# Copy_of_SX1276_e266v02a.net
KiCad netlist of a schematic drawn in Altium Designer
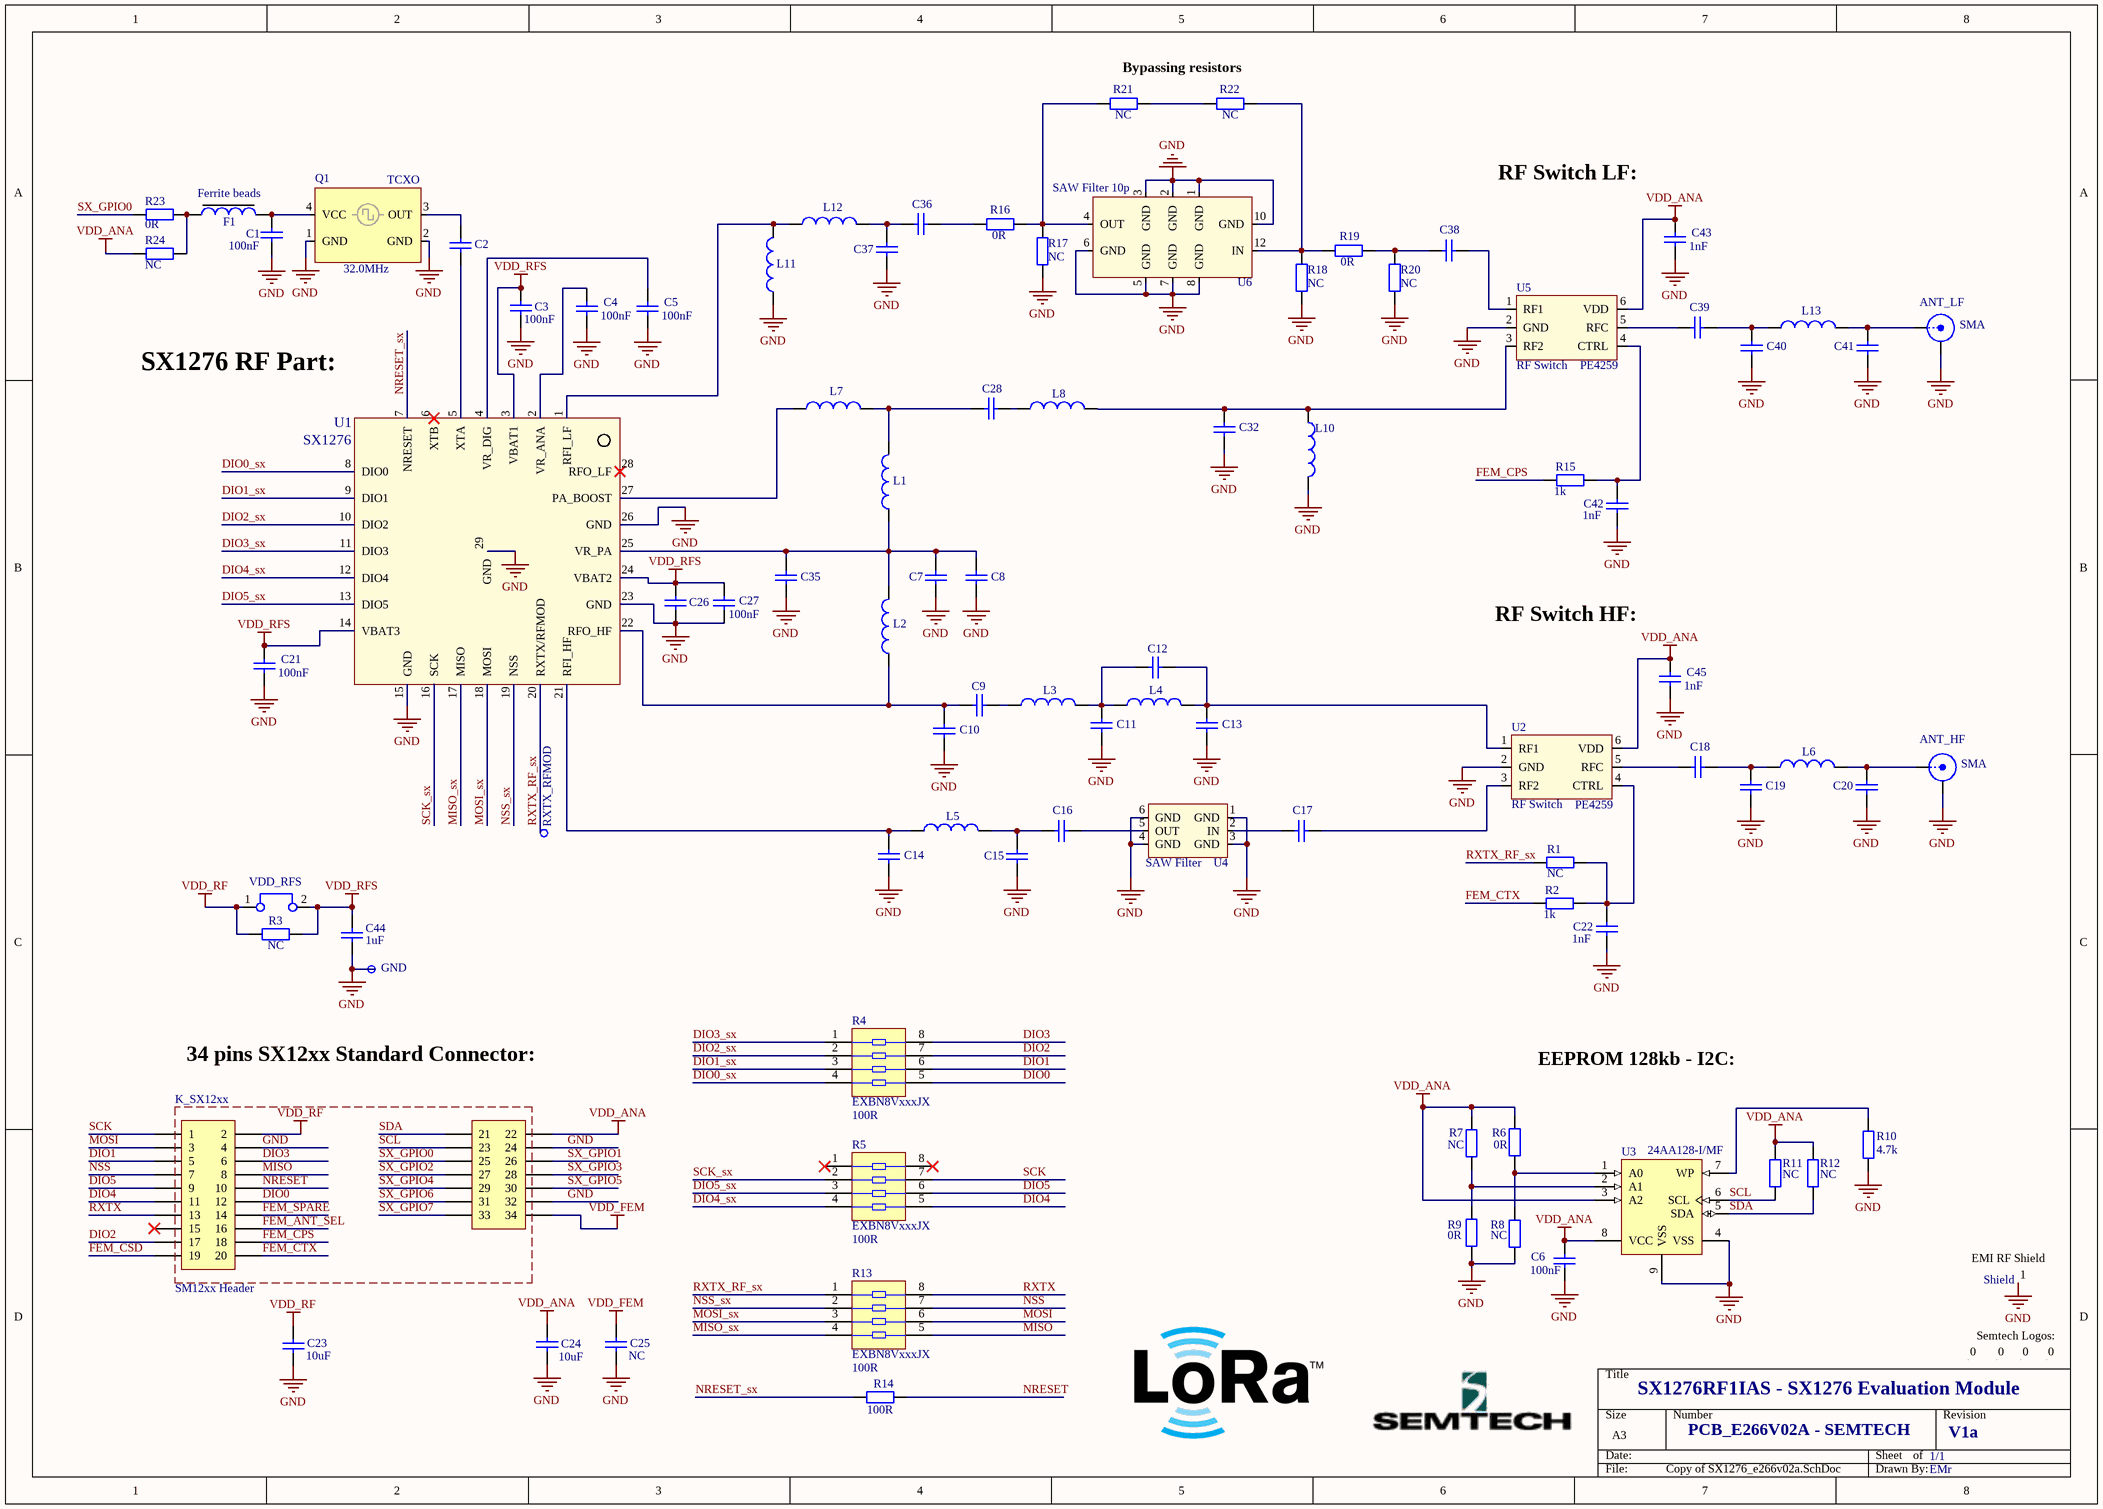
[diagram p0: Copy of SX1276_e266v02a.SchDoc]

(export (version "E")
  (design (tool "Eeschema 10.0.6"))
  (components
    (comp (ref "ANT_HF")
      (value "SMA")
      (footprint "SMA END LAUNCH JACK RECEPTACLE SHORT")
      (description "SMA Straight Connector")
      (fields (field (name "PUBLISHER") "Altium Limited"))
      (libsource (lib "SX1276_e266v02a") (part "SMA"))
    )
    (comp (ref "ANT_LF")
      (value "SMA")
      (footprint "SMA END LAUNCH JACK RECEPTACLE SHORT")
      (description "SMA Straight Connector")
      (fields (field (name "PUBLISHER") "Altium Limited"))
      (libsource (lib "SX1276_e266v02a") (part "SMA"))
    )
    (comp (ref "C1")
      (value "100nF")
      (footprint "rlc_402_smd")
      (description "Capacitor SMD")
      (fields (field (name "Comment") "Cap") (field (name "PUBLISHER") "Altium Limited"))
      (libsource (lib "SX1276_e266v02a") (part "Cap"))
    )
    (comp (ref "C2")
      (value "Cap")
      (footprint "rlc_402_smd")
      (description "Capacitor SMD")
      (fields (field (name "PUBLISHER") "Altium Limited"))
      (libsource (lib "SX1276_e266v02a") (part "Cap"))
    )
    (comp (ref "C3")
      (value "100nF")
      (footprint "rlc_402_smd")
      (description "Capacitor SMD")
      (fields (field (name "Comment") "Cap") (field (name "PUBLISHER") "Altium Limited"))
      (libsource (lib "SX1276_e266v02a") (part "Cap"))
    )
    (comp (ref "C4")
      (value "100nF")
      (footprint "rlc_402_smd")
      (description "Capacitor SMD")
      (fields (field (name "Comment") "Cap") (field (name "PUBLISHER") "Altium Limited"))
      (libsource (lib "SX1276_e266v02a") (part "Cap"))
    )
    (comp (ref "C5")
      (value "100nF")
      (footprint "rlc_402_smd")
      (description "Capacitor SMD")
      (fields (field (name "Comment") "Cap") (field (name "PUBLISHER") "Altium Limited"))
      (libsource (lib "SX1276_e266v02a") (part "Cap"))
    )
    (comp (ref "C6")
      (value "100nF")
      (footprint "rlc_402_smd")
      (description "Capacitor SMD")
      (fields (field (name "Comment") "Cap") (field (name "PUBLISHER") "Altium Limited"))
      (libsource (lib "SX1276_e266v02a") (part "Cap"))
    )
    (comp (ref "C7")
      (value "Cap")
      (footprint "rlc_402_smd")
      (description "Capacitor SMD")
      (fields (field (name "PUBLISHER") "Altium Limited"))
      (libsource (lib "SX1276_e266v02a") (part "Cap"))
    )
    (comp (ref "C8")
      (value "Cap")
      (footprint "rlc_402_smd")
      (description "Capacitor SMD")
      (fields (field (name "PUBLISHER") "Altium Limited"))
      (libsource (lib "SX1276_e266v02a") (part "Cap"))
    )
    (comp (ref "C9")
      (value "Cap")
      (footprint "rlc_402_smd")
      (description "Capacitor SMD")
      (fields (field (name "PUBLISHER") "Altium Limited"))
      (libsource (lib "SX1276_e266v02a") (part "Cap"))
    )
    (comp (ref "C10")
      (value "Cap")
      (footprint "rlc_402_smd")
      (description "Capacitor SMD")
      (fields (field (name "PUBLISHER") "Altium Limited"))
      (libsource (lib "SX1276_e266v02a") (part "Cap"))
    )
    (comp (ref "C11")
      (value "Cap")
      (footprint "rlc_402_smd")
      (description "Capacitor SMD")
      (fields (field (name "PUBLISHER") "Altium Limited"))
      (libsource (lib "SX1276_e266v02a") (part "Cap"))
    )
    (comp (ref "C12")
      (value "Cap")
      (footprint "rlc_402_smd")
      (description "Capacitor SMD")
      (fields (field (name "PUBLISHER") "Altium Limited"))
      (libsource (lib "SX1276_e266v02a") (part "Cap"))
    )
    (comp (ref "C13")
      (value "Cap")
      (footprint "rlc_402_smd")
      (description "Capacitor SMD")
      (fields (field (name "PUBLISHER") "Altium Limited"))
      (libsource (lib "SX1276_e266v02a") (part "Cap"))
    )
    (comp (ref "C14")
      (value "Cap")
      (footprint "rlc_402_smd")
      (description "Capacitor SMD")
      (fields (field (name "PUBLISHER") "Altium Limited"))
      (libsource (lib "SX1276_e266v02a") (part "Cap"))
    )
    (comp (ref "C15")
      (value "Cap")
      (footprint "rlc_402_smd")
      (description "Capacitor SMD")
      (fields (field (name "PUBLISHER") "Altium Limited"))
      (libsource (lib "SX1276_e266v02a") (part "Cap"))
    )
    (comp (ref "C16")
      (value "Cap")
      (footprint "rlc_402_smd")
      (description "Capacitor SMD")
      (fields (field (name "PUBLISHER") "Altium Limited"))
      (libsource (lib "SX1276_e266v02a") (part "Cap"))
    )
    (comp (ref "C17")
      (value "Cap")
      (footprint "rlc_402_smd")
      (description "Capacitor SMD")
      (fields (field (name "PUBLISHER") "Altium Limited"))
      (libsource (lib "SX1276_e266v02a") (part "Cap"))
    )
    (comp (ref "C18")
      (value "Cap")
      (footprint "rlc_402_smd")
      (description "Capacitor SMD")
      (fields (field (name "PUBLISHER") "Altium Limited"))
      (libsource (lib "SX1276_e266v02a") (part "Cap"))
    )
    (comp (ref "C19")
      (value "Cap")
      (footprint "rlc_402_smd")
      (description "Capacitor SMD")
      (fields (field (name "PUBLISHER") "Altium Limited"))
      (libsource (lib "SX1276_e266v02a") (part "Cap"))
    )
    (comp (ref "C20")
      (value "Cap")
      (footprint "rlc_402_smd")
      (description "Capacitor SMD")
      (fields (field (name "PUBLISHER") "Altium Limited"))
      (libsource (lib "SX1276_e266v02a") (part "Cap"))
    )
    (comp (ref "C21")
      (value "100nF")
      (footprint "rlc_402_smd")
      (description "Capacitor SMD")
      (fields (field (name "Comment") "Cap") (field (name "PUBLISHER") "Altium Limited"))
      (libsource (lib "SX1276_e266v02a") (part "Cap"))
    )
    (comp (ref "C22")
      (value "1nF")
      (footprint "rlc_402_smd")
      (description "Capacitor SMD")
      (fields (field (name "Comment") "Cap") (field (name "PUBLISHER") "Altium Limited"))
      (libsource (lib "SX1276_e266v02a") (part "Cap"))
    )
    (comp (ref "C23")
      (value "10uF")
      (footprint "rlc_805_smd")
      (description "Capacitor SMD")
      (fields (field (name "Comment") "Cap") (field (name "PUBLISHER") "Altium Limited"))
      (libsource (lib "SX1276_e266v02a") (part "Cap"))
    )
    (comp (ref "C24")
      (value "10uF")
      (footprint "rlc_805_smd")
      (description "Capacitor SMD")
      (fields (field (name "Comment") "Cap") (field (name "PUBLISHER") "Altium Limited"))
      (libsource (lib "SX1276_e266v02a") (part "Cap"))
    )
    (comp (ref "C25")
      (value "NC")
      (footprint "rlc_805_smd")
      (description "Capacitor SMD")
      (fields (field (name "Comment") "Cap") (field (name "PUBLISHER") "Altium Limited"))
      (libsource (lib "SX1276_e266v02a") (part "Cap"))
    )
    (comp (ref "C26")
      (value "Cap")
      (footprint "rlc_402_smd")
      (description "Capacitor SMD")
      (fields (field (name "PUBLISHER") "Altium Limited"))
      (libsource (lib "SX1276_e266v02a") (part "Cap"))
    )
    (comp (ref "C27")
      (value "100nF")
      (footprint "rlc_402_smd")
      (description "Capacitor SMD")
      (fields (field (name "Comment") "Cap") (field (name "PUBLISHER") "Altium Limited"))
      (libsource (lib "SX1276_e266v02a") (part "Cap"))
    )
    (comp (ref "C28")
      (value "Cap")
      (footprint "rlc_402_smd")
      (description "Capacitor SMD")
      (fields (field (name "PUBLISHER") "Altium Limited"))
      (libsource (lib "SX1276_e266v02a") (part "Cap"))
    )
    (comp (ref "C32")
      (value "Cap")
      (footprint "rlc_402_smd")
      (description "Capacitor SMD")
      (fields (field (name "PUBLISHER") "Altium Limited"))
      (libsource (lib "SX1276_e266v02a") (part "Cap"))
    )
    (comp (ref "C35")
      (value "Cap")
      (footprint "rlc_402_smd")
      (description "Capacitor SMD")
      (fields (field (name "PUBLISHER") "Altium Limited"))
      (libsource (lib "SX1276_e266v02a") (part "Cap"))
    )
    (comp (ref "C36")
      (value "Cap")
      (footprint "rlc_402_smd")
      (description "Capacitor SMD")
      (fields (field (name "PUBLISHER") "Altium Limited"))
      (libsource (lib "SX1276_e266v02a") (part "Cap"))
    )
    (comp (ref "C37")
      (value "Cap")
      (footprint "rlc_402_smd")
      (description "Capacitor SMD")
      (fields (field (name "PUBLISHER") "Altium Limited"))
      (libsource (lib "SX1276_e266v02a") (part "Cap"))
    )
    (comp (ref "C38")
      (value "Cap")
      (footprint "rlc_402_smd")
      (description "Capacitor SMD")
      (fields (field (name "PUBLISHER") "Altium Limited"))
      (libsource (lib "SX1276_e266v02a") (part "Cap"))
    )
    (comp (ref "C39")
      (value "Cap")
      (footprint "rlc_402_smd")
      (description "Capacitor SMD")
      (fields (field (name "PUBLISHER") "Altium Limited"))
      (libsource (lib "SX1276_e266v02a") (part "Cap"))
    )
    (comp (ref "C40")
      (value "Cap")
      (footprint "rlc_402_smd")
      (description "Capacitor SMD")
      (fields (field (name "PUBLISHER") "Altium Limited"))
      (libsource (lib "SX1276_e266v02a") (part "Cap"))
    )
    (comp (ref "C41")
      (value "Cap")
      (footprint "rlc_402_smd")
      (description "Capacitor SMD")
      (fields (field (name "PUBLISHER") "Altium Limited"))
      (libsource (lib "SX1276_e266v02a") (part "Cap"))
    )
    (comp (ref "C42")
      (value "1nF")
      (footprint "rlc_402_smd")
      (description "Capacitor SMD")
      (fields (field (name "Comment") "Cap") (field (name "PUBLISHER") "Altium Limited"))
      (libsource (lib "SX1276_e266v02a") (part "Cap"))
    )
    (comp (ref "C43")
      (value "1nF")
      (footprint "rlc_402_smd")
      (description "Capacitor SMD")
      (fields (field (name "Comment") "Cap") (field (name "PUBLISHER") "Altium Limited"))
      (libsource (lib "SX1276_e266v02a") (part "Cap"))
    )
    (comp (ref "C44")
      (value "1uF")
      (footprint "rlc_603_smd")
      (description "Capacitor (Semiconductor SIM Model)")
      (fields (field (name "Comment") "Cap Semi") (field (name "PUBLISHER") "Altium Limited"))
      (libsource (lib "SX1276_e266v02a") (part "Cap Semi"))
    )
    (comp (ref "C45")
      (value "1nF")
      (footprint "rlc_402_smd")
      (description "Capacitor SMD")
      (fields (field (name "Comment") "Cap") (field (name "PUBLISHER") "Altium Limited"))
      (libsource (lib "SX1276_e266v02a") (part "Cap"))
    )
    (comp (ref "F1")
      (value "Ferrite beads")
      (footprint "rlc_402_smd")
      (libsource (lib "SX1276_e266v02a") (part "Ferrite beads"))
    )
    (comp (ref "GND")
      (value "Test Pin")
      (footprint "pin_1mm")
      (libsource (lib "SX1276_e266v02a") (part "test_pin"))
    )
    (comp (ref "K_SX12xx")
      (value "SM12xx Header")
      (footprint "HDR34 Header")
      (description "SM12xx Header; 34pins: 2x10pins + 2x7pins")
      (fields (field (name "PUBLISHER") "Altium Limited"))
      (libsource (lib "SX1276_e266v02a") (part "SM12xx Header"))
    )
    (comp (ref "L1")
      (value "Inductor")
      (footprint "rlc_402_smd")
      (description "Inductor SMD")
      (fields (field (name "PUBLISHER") "Altium Limited"))
      (libsource (lib "SX1276_e266v02a") (part "Inductor"))
    )
    (comp (ref "L2")
      (value "Inductor")
      (footprint "rlc_402_smd")
      (description "Inductor SMD")
      (fields (field (name "PUBLISHER") "Altium Limited"))
      (libsource (lib "SX1276_e266v02a") (part "Inductor"))
    )
    (comp (ref "L3")
      (value "Inductor")
      (footprint "rlc_402_smd")
      (description "Inductor SMD")
      (fields (field (name "PUBLISHER") "Altium Limited"))
      (libsource (lib "SX1276_e266v02a") (part "Inductor"))
    )
    (comp (ref "L4")
      (value "Inductor")
      (footprint "rlc_402_smd")
      (description "Inductor SMD")
      (fields (field (name "PUBLISHER") "Altium Limited"))
      (libsource (lib "SX1276_e266v02a") (part "Inductor"))
    )
    (comp (ref "L5")
      (value "Inductor")
      (footprint "rlc_402_smd")
      (description "Inductor SMD")
      (fields (field (name "PUBLISHER") "Altium Limited"))
      (libsource (lib "SX1276_e266v02a") (part "Inductor"))
    )
    (comp (ref "L6")
      (value "Inductor")
      (footprint "rlc_402_smd")
      (description "Inductor SMD")
      (fields (field (name "PUBLISHER") "Altium Limited"))
      (libsource (lib "SX1276_e266v02a") (part "Inductor"))
    )
    (comp (ref "L7")
      (value "Inductor")
      (footprint "rlc_402_smd")
      (description "Inductor SMD")
      (fields (field (name "PUBLISHER") "Altium Limited"))
      (libsource (lib "SX1276_e266v02a") (part "Inductor"))
    )
    (comp (ref "L8")
      (value "Inductor")
      (footprint "rlc_402_smd")
      (description "Inductor SMD")
      (fields (field (name "PUBLISHER") "Altium Limited"))
      (libsource (lib "SX1276_e266v02a") (part "Inductor"))
    )
    (comp (ref "L10")
      (value "Inductor")
      (footprint "rlc_402_smd")
      (description "Inductor SMD")
      (fields (field (name "PUBLISHER") "Altium Limited"))
      (libsource (lib "SX1276_e266v02a") (part "Inductor"))
    )
    (comp (ref "L11")
      (value "Inductor")
      (footprint "rlc_402_smd")
      (description "Inductor SMD")
      (fields (field (name "PUBLISHER") "Altium Limited"))
      (libsource (lib "SX1276_e266v02a") (part "Inductor"))
    )
    (comp (ref "L12")
      (value "Inductor")
      (footprint "rlc_402_smd")
      (description "Inductor SMD")
      (fields (field (name "PUBLISHER") "Altium Limited"))
      (libsource (lib "SX1276_e266v02a") (part "Inductor"))
    )
    (comp (ref "L13")
      (value "Inductor")
      (footprint "rlc_402_smd")
      (description "Inductor SMD")
      (fields (field (name "PUBLISHER") "Altium Limited"))
      (libsource (lib "SX1276_e266v02a") (part "Inductor"))
    )
    (comp (ref "Logo Bot")
      (value "Logo symbol")
      (footprint "logo_semtech_horiz_size3")
      (description "Schematic symbol for Logo")
      (libsource (lib "SX1276_e266v02a") (part "Logo"))
    )
    (comp (ref "Logo Lora Bot")
      (value "Logo symbol")
      (footprint "Logo LoRa Size4")
      (description "Schematic symbol for Logo")
      (libsource (lib "SX1276_e266v02a") (part "Logo"))
    )
    (comp (ref "Logo Lora Top")
      (value "Logo symbol")
      (footprint "Logo LoRa Size3")
      (description "Schematic symbol for Logo")
      (libsource (lib "SX1276_e266v02a") (part "Logo"))
    )
    (comp (ref "Logo Top")
      (value "Logo symbol")
      (footprint "logo_semtech_horiz_size2")
      (description "Schematic symbol for Logo")
      (libsource (lib "SX1276_e266v02a") (part "Logo"))
    )
    (comp (ref "Q1")
      (value "TCXO")
      (footprint "IT3200C TCXO")
      (fields (field (name "ALTIUM_VALUE") "32.0MHz"))
      (libsource (lib "SX1276_e266v02a") (part "TCXO"))
    )
    (comp (ref "R1")
      (value "NC")
      (footprint "rlc_402_smd")
      (description "Resistor SMD - IEC symbol version")
      (fields (field (name "Comment") "Resistor"))
      (libsource (lib "") (part "Resistor_3"))
    )
    (comp (ref "R2")
      (value "1k")
      (footprint "rlc_402_smd")
      (description "Resistor SMD - IEC symbol version")
      (fields (field (name "Comment") "Resistor"))
      (libsource (lib "") (part "Resistor_2"))
    )
    (comp (ref "R3")
      (value "NC")
      (footprint "rlc_805_smd")
      (description "Resistor SMD - IEC symbol version")
      (fields (field (name "Comment") "Resistor"))
      (libsource (lib "") (part "Resistor_2"))
    )
    (comp (ref "R4")
      (value "EXBN8VxxxJX")
      (footprint "EXB28V")
      (description "Mini-Flat Package, Isolated Resistor Network, 0.031 W/resistor")
      (fields (field (name "ALTIUM_VALUE") "100R"))
      (libsource (lib "SX1276_e266v02a") (part "EXBN8VxxxJX"))
    )
    (comp (ref "R5")
      (value "EXBN8VxxxJX")
      (footprint "EXB28V")
      (description "Mini-Flat Package, Isolated Resistor Network, 0.031 W/resistor")
      (fields (field (name "ALTIUM_VALUE") "100R"))
      (libsource (lib "SX1276_e266v02a") (part "EXBN8VxxxJX"))
    )
    (comp (ref "R6")
      (value "0R")
      (footprint "rlc_402_smd")
      (description "Resistor SMD - IEC symbol version")
      (fields (field (name "Comment") "Resistor"))
      (libsource (lib "") (part "Resistor_3"))
    )
    (comp (ref "R7")
      (value "NC")
      (footprint "rlc_402_smd")
      (description "Resistor SMD - IEC symbol version")
      (fields (field (name "Comment") "Resistor"))
      (libsource (lib "") (part "Resistor_3"))
    )
    (comp (ref "R8")
      (value "NC")
      (footprint "rlc_402_smd")
      (description "Resistor SMD - IEC symbol version")
      (fields (field (name "Comment") "Resistor"))
      (libsource (lib "") (part "Resistor_3"))
    )
    (comp (ref "R9")
      (value "0R")
      (footprint "rlc_402_smd")
      (description "Resistor SMD - IEC symbol version")
      (fields (field (name "Comment") "Resistor"))
      (libsource (lib "") (part "Resistor_3"))
    )
    (comp (ref "R10")
      (value "4.7k")
      (footprint "rlc_402_smd")
      (description "Resistor SMD - IEC symbol version")
      (fields (field (name "Comment") "Resistor"))
      (libsource (lib "") (part "Resistor_3"))
    )
    (comp (ref "R11")
      (value "NC")
      (footprint "rlc_402_smd")
      (description "Resistor SMD - IEC symbol version")
      (fields (field (name "Comment") "Resistor"))
      (libsource (lib "") (part "Resistor_3"))
    )
    (comp (ref "R12")
      (value "NC")
      (footprint "rlc_402_smd")
      (description "Resistor SMD - IEC symbol version")
      (fields (field (name "Comment") "Resistor"))
      (libsource (lib "") (part "Resistor_3"))
    )
    (comp (ref "R13")
      (value "EXBN8VxxxJX")
      (footprint "EXB28V")
      (description "Mini-Flat Package, Isolated Resistor Network, 0.031 W/resistor")
      (fields (field (name "ALTIUM_VALUE") "100R"))
      (libsource (lib "SX1276_e266v02a") (part "EXBN8VxxxJX"))
    )
    (comp (ref "R14")
      (value "100R")
      (footprint "rlc_402_smd")
      (description "Resistor SMD - IEC symbol version")
      (fields (field (name "Comment") "Resistor"))
      (libsource (lib "") (part "Resistor_1"))
    )
    (comp (ref "R15")
      (value "1k")
      (footprint "rlc_402_smd")
      (description "Resistor SMD - IEC symbol version")
      (fields (field (name "Comment") "Resistor"))
      (libsource (lib "") (part "Resistor_2"))
    )
    (comp (ref "R16")
      (value "0R")
      (footprint "rlc_402_smd")
      (description "Resistor SMD - IEC symbol version")
      (fields (field (name "Comment") "Resistor"))
      (libsource (lib "") (part "Resistor_2"))
    )
    (comp (ref "R17")
      (value "NC")
      (footprint "rlc_402_smd")
      (description "Resistor SMD - IEC symbol version")
      (fields (field (name "Comment") "Resistor"))
      (libsource (lib "SX1276_e266v02a") (part "Resistor"))
    )
    (comp (ref "R18")
      (value "NC")
      (footprint "rlc_402_smd")
      (description "Resistor SMD - IEC symbol version")
      (fields (field (name "Comment") "Resistor"))
      (libsource (lib "SX1276_e266v02a") (part "Resistor"))
    )
    (comp (ref "R19")
      (value "0R")
      (footprint "rlc_402_smd")
      (description "Resistor SMD - IEC symbol version")
      (fields (field (name "Comment") "Resistor"))
      (libsource (lib "") (part "Resistor_2"))
    )
    (comp (ref "R20")
      (value "NC")
      (footprint "rlc_402_smd")
      (description "Resistor SMD - IEC symbol version")
      (fields (field (name "Comment") "Resistor"))
      (libsource (lib "SX1276_e266v02a") (part "Resistor"))
    )
    (comp (ref "R21")
      (value "NC")
      (footprint "rlc_402_smd")
      (description "Resistor SMD - IEC symbol version")
      (fields (field (name "Comment") "Resistor"))
      (libsource (lib "") (part "Resistor_2"))
    )
    (comp (ref "R22")
      (value "NC")
      (footprint "rlc_402_smd")
      (description "Resistor SMD - IEC symbol version")
      (fields (field (name "Comment") "Resistor"))
      (libsource (lib "") (part "Resistor_2"))
    )
    (comp (ref "R23")
      (value "0R")
      (footprint "rlc_402_smd")
      (description "Resistor SMD - IEC symbol version")
      (fields (field (name "Comment") "Resistor"))
      (libsource (lib "") (part "Resistor_3"))
    )
    (comp (ref "R24")
      (value "NC")
      (footprint "rlc_402_smd")
      (description "Resistor SMD - IEC symbol version")
      (fields (field (name "Comment") "Resistor"))
      (libsource (lib "") (part "Resistor_2"))
    )
    (comp (ref "RXTX_RFMOD")
      (value "Test Pin")
      (footprint "pin_SMD")
      (libsource (lib "SX1276_e266v02a") (part "test_pin"))
    )
    (comp (ref "Shield")
      (value "Logo symbol")
      (footprint "BMIS-205-F - Shield")
      (description "Shield - EMI Gasket - Standard Surface Mount Shields")
      (libsource (lib "SX1276_e266v02a") (part "Shield"))
    )
    (comp (ref "U1")
      (value "SX1276")
      (footprint "vqfn28_6x6mm")
      (description "SX1276 - Low Power Integrated UHF Transceiver with loRa Modem")
      (libsource (lib "SX1276_e266v02a") (part "SX1276"))
    )
    (comp (ref "U2")
      (value "RF Switch")
      (footprint "SC70-6")
      (description "PE4259 Peregrine RF Switch")
      (fields (field (name "ALTIUM_VALUE") "PE4259"))
      (libsource (lib "SX1276_e266v02a") (part "PE4259 RF Switch"))
    )
    (comp (ref "U3")
      (value "24AA128-I/MF")
      (footprint "DFN8_ 5x6mm")
      (description "128kbit, 400kHz, 1.7V, 8-Pin DFN, Industrial Temperature")
      (fields (field (name "PUBLISHER") "Altium Limited"))
      (libsource (lib "SX1276_e266v02a") (part "24AA128-I/MF"))
    )
    (comp (ref "U4")
      (value "SAW Filter")
      (footprint "DCC6C_3.0x3.0mm")
      (description "SAW Filter - Bandpass - TEMEX type")
      (libsource (lib "SX1276_e266v02a") (part "SAW Filter"))
    )
    (comp (ref "U5")
      (value "RF Switch")
      (footprint "SC70-6")
      (description "PE4259 Peregrine RF Switch")
      (fields (field (name "ALTIUM_VALUE") "PE4259"))
      (libsource (lib "SX1276_e266v02a") (part "PE4259 RF Switch"))
    )
    (comp (ref "U6")
      (value "SAW Filter 10p")
      (footprint "7.0x5.0mm SMD package")
      (description "SAW Filter 10p  - Bandpass - RFM type")
      (libsource (lib "SX1276_e266v02a") (part "SAW Filter 10p"))
    )
    (comp (ref "VDD_RFS")
      (value "Jumper")
      (footprint "bridge_254mm")
      (description "Jumper Wire")
      (libsource (lib "SX1276_e266v02a") (part "Jumper"))
    )
  )
  (nets
    (net (code "1") (name "/DIO0") (class "Default")
      (node (ref "K_SX12xx") (pin "12") (pinfunction "12_12") (pintype "passive"))
      (node (ref "R4") (pin "5") (pinfunction "5_5") (pintype "passive"))
    )
    (net (code "2") (name "/DIO0_sx") (class "Default")
      (node (ref "R4") (pin "4") (pinfunction "4_4") (pintype "passive"))
      (node (ref "U1") (pin "8") (pinfunction "DIO0_8") (pintype "passive"))
    )
    (net (code "3") (name "/DIO1") (class "Default")
      (node (ref "K_SX12xx") (pin "5") (pinfunction "5_5") (pintype "passive"))
      (node (ref "R4") (pin "6") (pinfunction "6_6") (pintype "passive"))
    )
    (net (code "4") (name "/DIO1_sx") (class "Default")
      (node (ref "R4") (pin "3") (pinfunction "3_3") (pintype "passive"))
      (node (ref "U1") (pin "9") (pinfunction "DIO1_9") (pintype "passive"))
    )
    (net (code "5") (name "/DIO2") (class "Default")
      (node (ref "K_SX12xx") (pin "17") (pinfunction "17_17") (pintype "passive"))
      (node (ref "R4") (pin "7") (pinfunction "7_7") (pintype "passive"))
    )
    (net (code "6") (name "/DIO2_sx") (class "Default")
      (node (ref "R4") (pin "2") (pinfunction "2_2") (pintype "passive"))
      (node (ref "U1") (pin "10") (pinfunction "DIO2_10") (pintype "passive"))
    )
    (net (code "7") (name "/DIO3") (class "Default")
      (node (ref "K_SX12xx") (pin "6") (pinfunction "6_6") (pintype "passive"))
      (node (ref "R4") (pin "8") (pinfunction "8_8") (pintype "passive"))
    )
    (net (code "8") (name "/DIO3_sx") (class "Default")
      (node (ref "R4") (pin "1") (pinfunction "1_1") (pintype "passive"))
      (node (ref "U1") (pin "11") (pinfunction "DIO3_11") (pintype "passive"))
    )
    (net (code "9") (name "/DIO4") (class "Default")
      (node (ref "K_SX12xx") (pin "11") (pinfunction "11_11") (pintype "passive"))
      (node (ref "R5") (pin "5") (pinfunction "5_5") (pintype "passive"))
    )
    (net (code "10") (name "/DIO4_sx") (class "Default")
      (node (ref "R5") (pin "4") (pinfunction "4_4") (pintype "passive"))
      (node (ref "U1") (pin "12") (pinfunction "DIO4_12") (pintype "passive"))
    )
    (net (code "11") (name "/DIO5") (class "Default")
      (node (ref "K_SX12xx") (pin "9") (pinfunction "9_9") (pintype "passive"))
      (node (ref "R5") (pin "6") (pinfunction "6_6") (pintype "passive"))
    )
    (net (code "12") (name "/DIO5_sx") (class "Default")
      (node (ref "R5") (pin "3") (pinfunction "3_3") (pintype "passive"))
      (node (ref "U1") (pin "13") (pinfunction "DIO5_13") (pintype "passive"))
    )
    (net (code "13") (name "/FEM_ANT_SEL") (class "Default")
      (node (ref "K_SX12xx") (pin "16") (pinfunction "16_16") (pintype "passive"))
    )
    (net (code "14") (name "/FEM_CPS") (class "Default")
      (node (ref "K_SX12xx") (pin "18") (pinfunction "18_18") (pintype "passive"))
      (node (ref "R15") (pin "2") (pinfunction "2_2") (pintype "passive"))
    )
    (net (code "15") (name "/FEM_CSD") (class "Default")
      (node (ref "K_SX12xx") (pin "19") (pinfunction "19_19") (pintype "passive"))
    )
    (net (code "16") (name "/FEM_CTX") (class "Default")
      (node (ref "K_SX12xx") (pin "20") (pinfunction "20_20") (pintype "passive"))
      (node (ref "R2") (pin "2") (pinfunction "2_2") (pintype "passive"))
    )
    (net (code "17") (name "/FEM_SPARE") (class "Default")
      (node (ref "K_SX12xx") (pin "14") (pinfunction "14_14") (pintype "passive"))
    )
    (net (code "18") (name "/MISO") (class "Default")
      (node (ref "K_SX12xx") (pin "8") (pinfunction "8_8") (pintype "passive"))
      (node (ref "R13") (pin "5") (pinfunction "5_5") (pintype "passive"))
    )
    (net (code "19") (name "/MISO_sx") (class "Default")
      (node (ref "R13") (pin "4") (pinfunction "4_4") (pintype "passive"))
      (node (ref "U1") (pin "17") (pinfunction "MISO_17") (pintype "passive"))
    )
    (net (code "20") (name "/MOSI") (class "Default")
      (node (ref "K_SX12xx") (pin "3") (pinfunction "3_3") (pintype "passive"))
      (node (ref "R13") (pin "6") (pinfunction "6_6") (pintype "passive"))
    )
    (net (code "21") (name "/MOSI_sx") (class "Default")
      (node (ref "R13") (pin "3") (pinfunction "3_3") (pintype "passive"))
      (node (ref "U1") (pin "18") (pinfunction "MOSI_18") (pintype "passive"))
    )
    (net (code "22") (name "/NRESET") (class "Default")
      (node (ref "K_SX12xx") (pin "10") (pinfunction "10_10") (pintype "passive"))
      (node (ref "R14") (pin "2") (pinfunction "2_2") (pintype "passive"))
    )
    (net (code "23") (name "/NRESET_sx") (class "Default")
      (node (ref "R14") (pin "1") (pinfunction "1_1") (pintype "passive"))
      (node (ref "U1") (pin "7") (pinfunction "NRESET_7") (pintype "passive"))
    )
    (net (code "24") (name "/NSS") (class "Default")
      (node (ref "K_SX12xx") (pin "7") (pinfunction "7_7") (pintype "passive"))
      (node (ref "R13") (pin "7") (pinfunction "7_7") (pintype "passive"))
    )
    (net (code "25") (name "/NSS_sx") (class "Default")
      (node (ref "R13") (pin "2") (pinfunction "2_2") (pintype "passive"))
      (node (ref "U1") (pin "19") (pinfunction "NSS_19") (pintype "passive"))
    )
    (net (code "26") (name "/RXTX") (class "Default")
      (node (ref "K_SX12xx") (pin "13") (pinfunction "13_13") (pintype "passive"))
      (node (ref "R13") (pin "8") (pinfunction "8_8") (pintype "passive"))
    )
    (net (code "27") (name "/RXTX_RF_sx") (class "Default")
      (node (ref "R1") (pin "1") (pinfunction "1_1") (pintype "passive"))
      (node (ref "R13") (pin "1") (pinfunction "1_1") (pintype "passive"))
      (node (ref "RXTX_RFMOD") (pin "1") (pinfunction "pin_1") (pintype "passive"))
      (node (ref "U1") (pin "20") (pinfunction "RXTX/RFMOD_20") (pintype "passive"))
    )
    (net (code "28") (name "/SCK") (class "Default")
      (node (ref "K_SX12xx") (pin "1") (pinfunction "1_1") (pintype "passive"))
      (node (ref "R5") (pin "7") (pinfunction "7_7") (pintype "passive"))
    )
    (net (code "29") (name "/SCK_sx") (class "Default")
      (node (ref "R5") (pin "2") (pinfunction "2_2") (pintype "passive"))
      (node (ref "U1") (pin "16") (pinfunction "SCK_16") (pintype "passive"))
    )
    (net (code "30") (name "/SCL") (class "Default")
      (node (ref "K_SX12xx") (pin "23") (pinfunction "23_23") (pintype "passive"))
      (node (ref "R11") (pin "1") (pinfunction "1_1") (pintype "passive"))
      (node (ref "U3") (pin "6") (pinfunction "SCL_6") (pintype "input"))
    )
    (net (code "31") (name "/SDA") (class "Default")
      (node (ref "K_SX12xx") (pin "21") (pinfunction "21_21") (pintype "passive"))
      (node (ref "R12") (pin "1") (pinfunction "1_1") (pintype "passive"))
      (node (ref "U3") (pin "5") (pinfunction "SDA_5") (pintype "bidirectional"))
    )
    (net (code "32") (name "/SX_GPIO0") (class "Default")
      (node (ref "K_SX12xx") (pin "25") (pinfunction "25_25") (pintype "passive"))
      (node (ref "R23") (pin "1") (pinfunction "1_1") (pintype "passive"))
    )
    (net (code "33") (name "/SX_GPIO1") (class "Default")
      (node (ref "K_SX12xx") (pin "26") (pinfunction "26_26") (pintype "passive"))
    )
    (net (code "34") (name "/SX_GPIO2") (class "Default")
      (node (ref "K_SX12xx") (pin "27") (pinfunction "27_27") (pintype "passive"))
    )
    (net (code "35") (name "/SX_GPIO3") (class "Default")
      (node (ref "K_SX12xx") (pin "28") (pinfunction "28_28") (pintype "passive"))
    )
    (net (code "36") (name "/SX_GPIO4") (class "Default")
      (node (ref "K_SX12xx") (pin "29") (pinfunction "29_29") (pintype "passive"))
    )
    (net (code "37") (name "/SX_GPIO5") (class "Default")
      (node (ref "K_SX12xx") (pin "30") (pinfunction "30_30") (pintype "passive"))
    )
    (net (code "38") (name "/SX_GPIO6") (class "Default")
      (node (ref "K_SX12xx") (pin "31") (pinfunction "31_31") (pintype "passive"))
    )
    (net (code "39") (name "/SX_GPIO7") (class "Default")
      (node (ref "K_SX12xx") (pin "33") (pinfunction "33_33") (pintype "passive"))
    )
    (net (code "40") (name "GND") (class "Default")
      (node (ref "ANT_HF") (pin "2") (pinfunction "GND_2") (pintype "passive"))
      (node (ref "ANT_LF") (pin "2") (pinfunction "GND_2") (pintype "passive"))
      (node (ref "C1") (pin "1") (pinfunction "1_1") (pintype "passive"))
      (node (ref "C10") (pin "1") (pinfunction "1_1") (pintype "passive"))
      (node (ref "C11") (pin "1") (pinfunction "1_1") (pintype "passive"))
      (node (ref "C13") (pin "1") (pinfunction "1_1") (pintype "passive"))
      (node (ref "C14") (pin "1") (pinfunction "1_1") (pintype "passive"))
      (node (ref "C15") (pin "1") (pinfunction "1_1") (pintype "passive"))
      (node (ref "C19") (pin "1") (pinfunction "1_1") (pintype "passive"))
      (node (ref "C20") (pin "1") (pinfunction "1_1") (pintype "passive"))
      (node (ref "C21") (pin "1") (pinfunction "1_1") (pintype "passive"))
      (node (ref "C22") (pin "2") (pinfunction "2_2") (pintype "passive"))
      (node (ref "C23") (pin "1") (pinfunction "1_1") (pintype "passive"))
      (node (ref "C24") (pin "1") (pinfunction "1_1") (pintype "passive"))
      (node (ref "C25") (pin "2") (pinfunction "2_2") (pintype "passive"))
      (node (ref "C26") (pin "1") (pinfunction "1_1") (pintype "passive"))
      (node (ref "C27") (pin "1") (pinfunction "1_1") (pintype "passive"))
      (node (ref "C3") (pin "1") (pinfunction "1_1") (pintype "passive"))
      (node (ref "C32") (pin "1") (pinfunction "1_1") (pintype "passive"))
      (node (ref "C35") (pin "1") (pinfunction "1_1") (pintype "passive"))
      (node (ref "C37") (pin "1") (pinfunction "1_1") (pintype "passive"))
      (node (ref "C4") (pin "1") (pinfunction "1_1") (pintype "passive"))
      (node (ref "C40") (pin "1") (pinfunction "1_1") (pintype "passive"))
      (node (ref "C41") (pin "1") (pinfunction "1_1") (pintype "passive"))
      (node (ref "C42") (pin "2") (pinfunction "2_2") (pintype "passive"))
      (node (ref "C43") (pin "1") (pinfunction "1_1") (pintype "passive"))
      (node (ref "C44") (pin "1") (pinfunction "1_1") (pintype "passive"))
      (node (ref "C45") (pin "1") (pinfunction "1_1") (pintype "passive"))
      (node (ref "C5") (pin "1") (pinfunction "1_1") (pintype "passive"))
      (node (ref "C6") (pin "1") (pinfunction "1_1") (pintype "passive"))
      (node (ref "C7") (pin "1") (pinfunction "1_1") (pintype "passive"))
      (node (ref "C8") (pin "1") (pinfunction "1_1") (pintype "passive"))
      (node (ref "GND") (pin "1") (pinfunction "pin_1") (pintype "passive"))
      (node (ref "K_SX12xx") (pin "24") (pinfunction "24_24") (pintype "passive"))
      (node (ref "K_SX12xx") (pin "32") (pinfunction "32_32") (pintype "passive"))
      (node (ref "K_SX12xx") (pin "4") (pinfunction "4_4") (pintype "passive"))
      (node (ref "L10") (pin "2") (pinfunction "2_2") (pintype "passive"))
      (node (ref "L11") (pin "1") (pinfunction "1_1") (pintype "passive"))
      (node (ref "Q1") (pin "1") (pinfunction "GND_1") (pintype "passive"))
      (node (ref "Q1") (pin "2") (pinfunction "GND_2") (pintype "passive"))
      (node (ref "R10") (pin "1") (pinfunction "1_1") (pintype "passive"))
      (node (ref "R17") (pin "2") (pinfunction "2_2") (pintype "passive"))
      (node (ref "R18") (pin "2") (pinfunction "2_2") (pintype "passive"))
      (node (ref "R20") (pin "2") (pinfunction "2_2") (pintype "passive"))
      (node (ref "R8") (pin "1") (pinfunction "1_1") (pintype "passive"))
      (node (ref "R9") (pin "1") (pinfunction "1_1") (pintype "passive"))
      (node (ref "Shield") (pin "1") (pinfunction "1_1") (pintype "passive"))
      (node (ref "U1") (pin "15") (pinfunction "GND_15") (pintype "passive"))
      (node (ref "U1") (pin "23") (pinfunction "GND_23") (pintype "passive"))
      (node (ref "U1") (pin "26") (pinfunction "GND_26") (pintype "passive"))
      (node (ref "U1") (pin "29") (pinfunction "GND_29") (pintype "passive"))
      (node (ref "U2") (pin "2") (pinfunction "GND_2") (pintype "passive"))
      (node (ref "U3") (pin "4") (pinfunction "VSS_4") (pintype "power_in"))
      (node (ref "U3") (pin "9") (pinfunction "VSS_9") (pintype "power_in"))
      (node (ref "U4") (pin "1") (pinfunction "GND_1") (pintype "passive"))
      (node (ref "U4") (pin "3") (pinfunction "GND_3") (pintype "passive"))
      (node (ref "U4") (pin "4") (pinfunction "GND_4") (pintype "passive"))
      (node (ref "U4") (pin "6") (pinfunction "GND_6") (pintype "passive"))
      (node (ref "U5") (pin "2") (pinfunction "GND_2") (pintype "passive"))
      (node (ref "U6") (pin "1") (pinfunction "GND_1") (pintype "passive"))
      (node (ref "U6") (pin "10") (pinfunction "GND_10") (pintype "passive"))
      (node (ref "U6") (pin "2") (pinfunction "GND_2") (pintype "passive"))
      (node (ref "U6") (pin "3") (pinfunction "GND_3") (pintype "passive"))
      (node (ref "U6") (pin "5") (pinfunction "GND_5") (pintype "passive"))
      (node (ref "U6") (pin "6") (pinfunction "GND_6") (pintype "passive"))
      (node (ref "U6") (pin "7") (pinfunction "GND_7") (pintype "passive"))
      (node (ref "U6") (pin "8") (pinfunction "GND_8") (pintype "passive"))
    )
    (net (code "41") (name "Net-(ANT_HF-Signal)") (class "Default")
      (node (ref "ANT_HF") (pin "1") (pinfunction "Signal_1") (pintype "passive"))
      (node (ref "C20") (pin "2") (pinfunction "2_2") (pintype "passive"))
      (node (ref "L6") (pin "2") (pinfunction "2_2") (pintype "passive"))
    )
    (net (code "42") (name "Net-(ANT_LF-Signal)") (class "Default")
      (node (ref "ANT_LF") (pin "1") (pinfunction "Signal_1") (pintype "passive"))
      (node (ref "C41") (pin "2") (pinfunction "2_2") (pintype "passive"))
      (node (ref "L13") (pin "2") (pinfunction "2_2") (pintype "passive"))
    )
    (net (code "43") (name "Net-(C9-Pad1)") (class "Default")
      (node (ref "C9") (pin "1") (pinfunction "1_1") (pintype "passive"))
      (node (ref "L3") (pin "1") (pinfunction "1_1") (pintype "passive"))
    )
    (net (code "44") (name "Net-(C11-Pad2)") (class "Default")
      (node (ref "C11") (pin "2") (pinfunction "2_2") (pintype "passive"))
      (node (ref "C12") (pin "2") (pinfunction "2_2") (pintype "passive"))
      (node (ref "L3") (pin "2") (pinfunction "2_2") (pintype "passive"))
      (node (ref "L4") (pin "1") (pinfunction "1_1") (pintype "passive"))
    )
    (net (code "45") (name "Net-(C15-Pad2)") (class "Default")
      (node (ref "C15") (pin "2") (pinfunction "2_2") (pintype "passive"))
      (node (ref "C16") (pin "2") (pinfunction "2_2") (pintype "passive"))
      (node (ref "L5") (pin "2") (pinfunction "2_2") (pintype "passive"))
    )
    (net (code "46") (name "Net-(C18-Pad1)") (class "Default")
      (node (ref "C18") (pin "1") (pinfunction "1_1") (pintype "passive"))
      (node (ref "C19") (pin "2") (pinfunction "2_2") (pintype "passive"))
      (node (ref "L6") (pin "1") (pinfunction "1_1") (pintype "passive"))
    )
    (net (code "47") (name "Net-(C28-Pad1)") (class "Default")
      (node (ref "C28") (pin "1") (pinfunction "1_1") (pintype "passive"))
      (node (ref "L8") (pin "1") (pinfunction "1_1") (pintype "passive"))
    )
    (net (code "48") (name "Net-(C28-Pad2)") (class "Default")
      (node (ref "C28") (pin "2") (pinfunction "2_2") (pintype "passive"))
      (node (ref "L1") (pin "2") (pinfunction "2_2") (pintype "passive"))
      (node (ref "L7") (pin "2") (pinfunction "2_2") (pintype "passive"))
    )
    (net (code "49") (name "Net-(C36-Pad1)") (class "Default")
      (node (ref "C36") (pin "1") (pinfunction "1_1") (pintype "passive"))
      (node (ref "R16") (pin "2") (pinfunction "2_2") (pintype "passive"))
    )
    (net (code "50") (name "Net-(C36-Pad2)") (class "Default")
      (node (ref "C36") (pin "2") (pinfunction "2_2") (pintype "passive"))
      (node (ref "C37") (pin "2") (pinfunction "2_2") (pintype "passive"))
      (node (ref "L12") (pin "2") (pinfunction "2_2") (pintype "passive"))
    )
    (net (code "51") (name "Net-(C38-Pad2)") (class "Default")
      (node (ref "C38") (pin "2") (pinfunction "2_2") (pintype "passive"))
      (node (ref "R19") (pin "1") (pinfunction "1_1") (pintype "passive"))
      (node (ref "R20") (pin "1") (pinfunction "1_1") (pintype "passive"))
    )
    (net (code "52") (name "Net-(C39-Pad1)") (class "Default")
      (node (ref "C39") (pin "1") (pinfunction "1_1") (pintype "passive"))
      (node (ref "C40") (pin "2") (pinfunction "2_2") (pintype "passive"))
      (node (ref "L13") (pin "1") (pinfunction "1_1") (pintype "passive"))
    )
    (net (code "53") (name "Net-(F1-Pad1)") (class "Default")
      (node (ref "F1") (pin "1") (pinfunction "1_1") (pintype "passive"))
      (node (ref "R23") (pin "2") (pinfunction "2_2") (pintype "passive"))
      (node (ref "R24") (pin "1") (pinfunction "1_1") (pintype "passive"))
    )
    (net (code "54") (name "Net-(Q1-OUT)") (class "Default")
      (node (ref "C2") (pin "1") (pinfunction "1_1") (pintype "passive"))
      (node (ref "Q1") (pin "3") (pinfunction "OUT_3") (pintype "passive"))
    )
    (net (code "55") (name "Net-(Q1-VCC)") (class "Default")
      (node (ref "C1") (pin "2") (pinfunction "2_2") (pintype "passive"))
      (node (ref "F1") (pin "2") (pinfunction "2_2") (pintype "passive"))
      (node (ref "Q1") (pin "4") (pinfunction "VCC_4") (pintype "passive"))
    )
    (net (code "56") (name "Net-(R21-Pad1)") (class "Default")
      (node (ref "R21") (pin "1") (pinfunction "1_1") (pintype "passive"))
      (node (ref "R22") (pin "2") (pinfunction "2_2") (pintype "passive"))
    )
    (net (code "57") (name "Net-(U1-PA_BOOST)") (class "Default")
      (node (ref "L7") (pin "1") (pinfunction "1_1") (pintype "passive"))
      (node (ref "U1") (pin "27") (pinfunction "PA_BOOST_27") (pintype "passive"))
    )
    (net (code "58") (name "Net-(U1-RFI_HF)") (class "Default")
      (node (ref "C14") (pin "2") (pinfunction "2_2") (pintype "passive"))
      (node (ref "L5") (pin "1") (pinfunction "1_1") (pintype "passive"))
      (node (ref "U1") (pin "21") (pinfunction "RFI_HF_21") (pintype "passive"))
    )
    (net (code "59") (name "Net-(U1-RFI_LF)") (class "Default")
      (node (ref "L11") (pin "2") (pinfunction "2_2") (pintype "passive"))
      (node (ref "L12") (pin "1") (pinfunction "1_1") (pintype "passive"))
      (node (ref "U1") (pin "1") (pinfunction "RFI_LF_1") (pintype "passive"))
    )
    (net (code "60") (name "Net-(U1-RFO_HF)") (class "Default")
      (node (ref "C10") (pin "2") (pinfunction "2_2") (pintype "passive"))
      (node (ref "C9") (pin "2") (pinfunction "2_2") (pintype "passive"))
      (node (ref "L2") (pin "1") (pinfunction "1_1") (pintype "passive"))
      (node (ref "U1") (pin "22") (pinfunction "RFO_HF_22") (pintype "passive"))
    )
    (net (code "61") (name "Net-(U1-VR_ANA)") (class "Default")
      (node (ref "C4") (pin "2") (pinfunction "2_2") (pintype "passive"))
      (node (ref "U1") (pin "2") (pinfunction "VR_ANA_2") (pintype "passive"))
    )
    (net (code "62") (name "Net-(U1-VR_DIG)") (class "Default")
      (node (ref "C5") (pin "2") (pinfunction "2_2") (pintype "passive"))
      (node (ref "U1") (pin "4") (pinfunction "VR_DIG_4") (pintype "passive"))
    )
    (net (code "63") (name "Net-(U1-VR_PA)") (class "Default")
      (node (ref "C35") (pin "2") (pinfunction "2_2") (pintype "passive"))
      (node (ref "C7") (pin "2") (pinfunction "2_2") (pintype "passive"))
      (node (ref "C8") (pin "2") (pinfunction "2_2") (pintype "passive"))
      (node (ref "L1") (pin "1") (pinfunction "1_1") (pintype "passive"))
      (node (ref "L2") (pin "2") (pinfunction "2_2") (pintype "passive"))
      (node (ref "U1") (pin "25") (pinfunction "VR_PA_25") (pintype "passive"))
    )
    (net (code "64") (name "Net-(U1-XTA)") (class "Default")
      (node (ref "C2") (pin "2") (pinfunction "2_2") (pintype "passive"))
      (node (ref "U1") (pin "5") (pinfunction "XTA_5") (pintype "passive"))
    )
    (net (code "65") (name "Net-(U2-CTRL)") (class "Default")
      (node (ref "C22") (pin "1") (pinfunction "1_1") (pintype "passive"))
      (node (ref "R1") (pin "2") (pinfunction "2_2") (pintype "passive"))
      (node (ref "R2") (pin "1") (pinfunction "1_1") (pintype "passive"))
      (node (ref "U2") (pin "4") (pinfunction "CTRL_4") (pintype "passive"))
    )
    (net (code "66") (name "Net-(U2-RF1)") (class "Default")
      (node (ref "C12") (pin "1") (pinfunction "1_1") (pintype "passive"))
      (node (ref "C13") (pin "2") (pinfunction "2_2") (pintype "passive"))
      (node (ref "L4") (pin "2") (pinfunction "2_2") (pintype "passive"))
      (node (ref "U2") (pin "1") (pinfunction "RF1_1") (pintype "passive"))
    )
    (net (code "67") (name "Net-(U2-RF2)") (class "Default")
      (node (ref "C17") (pin "1") (pinfunction "1_1") (pintype "passive"))
      (node (ref "U2") (pin "3") (pinfunction "RF2_3") (pintype "passive"))
    )
    (net (code "68") (name "Net-(U2-RFC)") (class "Default")
      (node (ref "C18") (pin "2") (pinfunction "2_2") (pintype "passive"))
      (node (ref "U2") (pin "5") (pinfunction "RFC_5") (pintype "passive"))
    )
    (net (code "69") (name "Net-(U3-A0)") (class "Default")
      (node (ref "R6") (pin "1") (pinfunction "1_1") (pintype "passive"))
      (node (ref "R8") (pin "2") (pinfunction "2_2") (pintype "passive"))
      (node (ref "U3") (pin "1") (pinfunction "A0_1") (pintype "input"))
    )
    (net (code "70") (name "Net-(U3-A1)") (class "Default")
      (node (ref "R7") (pin "1") (pinfunction "1_1") (pintype "passive"))
      (node (ref "R9") (pin "2") (pinfunction "2_2") (pintype "passive"))
      (node (ref "U3") (pin "2") (pinfunction "A1_2") (pintype "input"))
    )
    (net (code "71") (name "Net-(U3-WP)") (class "Default")
      (node (ref "R10") (pin "2") (pinfunction "2_2") (pintype "passive"))
      (node (ref "U3") (pin "7") (pinfunction "WP_7") (pintype "input"))
    )
    (net (code "72") (name "Net-(U4-IN)") (class "Default")
      (node (ref "C17") (pin "2") (pinfunction "2_2") (pintype "passive"))
      (node (ref "U4") (pin "2") (pinfunction "IN_2") (pintype "passive"))
    )
    (net (code "73") (name "Net-(U4-OUT)") (class "Default")
      (node (ref "C16") (pin "1") (pinfunction "1_1") (pintype "passive"))
      (node (ref "U4") (pin "5") (pinfunction "OUT_5") (pintype "passive"))
    )
    (net (code "74") (name "Net-(U5-CTRL)") (class "Default")
      (node (ref "C42") (pin "1") (pinfunction "1_1") (pintype "passive"))
      (node (ref "R15") (pin "1") (pinfunction "1_1") (pintype "passive"))
      (node (ref "U5") (pin "4") (pinfunction "CTRL_4") (pintype "passive"))
    )
    (net (code "75") (name "Net-(U5-RF1)") (class "Default")
      (node (ref "C38") (pin "1") (pinfunction "1_1") (pintype "passive"))
      (node (ref "U5") (pin "1") (pinfunction "RF1_1") (pintype "passive"))
    )
    (net (code "76") (name "Net-(U5-RF2)") (class "Default")
      (node (ref "C32") (pin "2") (pinfunction "2_2") (pintype "passive"))
      (node (ref "L10") (pin "1") (pinfunction "1_1") (pintype "passive"))
      (node (ref "L8") (pin "2") (pinfunction "2_2") (pintype "passive"))
      (node (ref "U5") (pin "3") (pinfunction "RF2_3") (pintype "passive"))
    )
    (net (code "77") (name "Net-(U5-RFC)") (class "Default")
      (node (ref "C39") (pin "2") (pinfunction "2_2") (pintype "passive"))
      (node (ref "U5") (pin "5") (pinfunction "RFC_5") (pintype "passive"))
    )
    (net (code "78") (name "Net-(U6-IN)") (class "Default")
      (node (ref "R18") (pin "1") (pinfunction "1_1") (pintype "passive"))
      (node (ref "R19") (pin "2") (pinfunction "2_2") (pintype "passive"))
      (node (ref "R22") (pin "1") (pinfunction "1_1") (pintype "passive"))
      (node (ref "U6") (pin "12") (pinfunction "IN_12") (pintype "passive"))
    )
    (net (code "79") (name "Net-(U6-OUT)") (class "Default")
      (node (ref "R16") (pin "1") (pinfunction "1_1") (pintype "passive"))
      (node (ref "R17") (pin "1") (pinfunction "1_1") (pintype "passive"))
      (node (ref "R21") (pin "2") (pinfunction "2_2") (pintype "passive"))
      (node (ref "U6") (pin "4") (pinfunction "OUT_4") (pintype "passive"))
    )
    (net (code "80") (name "VDD_ANA") (class "Default")
      (node (ref "C24") (pin "2") (pinfunction "2_2") (pintype "passive"))
      (node (ref "C43") (pin "2") (pinfunction "2_2") (pintype "passive"))
      (node (ref "C45") (pin "2") (pinfunction "2_2") (pintype "passive"))
      (node (ref "C6") (pin "2") (pinfunction "2_2") (pintype "passive"))
      (node (ref "K_SX12xx") (pin "22") (pinfunction "22_22") (pintype "passive"))
      (node (ref "R11") (pin "2") (pinfunction "2_2") (pintype "passive"))
      (node (ref "R12") (pin "2") (pinfunction "2_2") (pintype "passive"))
      (node (ref "R24") (pin "2") (pinfunction "2_2") (pintype "passive"))
      (node (ref "R6") (pin "2") (pinfunction "2_2") (pintype "passive"))
      (node (ref "R7") (pin "2") (pinfunction "2_2") (pintype "passive"))
      (node (ref "U2") (pin "6") (pinfunction "VDD_6") (pintype "passive"))
      (node (ref "U3") (pin "3") (pinfunction "A2_3") (pintype "input"))
      (node (ref "U3") (pin "8") (pinfunction "VCC_8") (pintype "power_in"))
      (node (ref "U5") (pin "6") (pinfunction "VDD_6") (pintype "passive"))
    )
    (net (code "81") (name "VDD_FEM") (class "Default")
      (node (ref "C25") (pin "1") (pinfunction "1_1") (pintype "passive"))
      (node (ref "K_SX12xx") (pin "34") (pinfunction "34_34") (pintype "passive"))
    )
    (net (code "82") (name "VDD_RF") (class "Default")
      (node (ref "C23") (pin "2") (pinfunction "2_2") (pintype "passive"))
      (node (ref "K_SX12xx") (pin "2") (pinfunction "2_2") (pintype "passive"))
      (node (ref "R3") (pin "2") (pinfunction "2_2") (pintype "passive"))
      (node (ref "VDD_RFS") (pin "1") (pinfunction "1_1") (pintype "passive"))
    )
    (net (code "83") (name "VDD_RFS") (class "Default")
      (node (ref "C21") (pin "2") (pinfunction "2_2") (pintype "passive"))
      (node (ref "C26") (pin "2") (pinfunction "2_2") (pintype "passive"))
      (node (ref "C27") (pin "2") (pinfunction "2_2") (pintype "passive"))
      (node (ref "C3") (pin "2") (pinfunction "2_2") (pintype "passive"))
      (node (ref "C44") (pin "2") (pinfunction "2_2") (pintype "passive"))
      (node (ref "R3") (pin "1") (pinfunction "1_1") (pintype "passive"))
      (node (ref "U1") (pin "14") (pinfunction "VBAT3_14") (pintype "passive"))
      (node (ref "U1") (pin "24") (pinfunction "VBAT2_24") (pintype "passive"))
      (node (ref "U1") (pin "3") (pinfunction "VBAT1_3") (pintype "passive"))
      (node (ref "VDD_RFS") (pin "2") (pinfunction "2_2") (pintype "passive"))
    )
    (net (code "84") (name "unconnected-(K_SX12xx-Pad15)") (class "Default")
      (node (ref "K_SX12xx") (pin "15") (pinfunction "15_15") (pintype "passive+no_connect"))
    )
    (net (code "85") (name "unconnected-(Logo Bot-Pad0)") (class "Default")
      (node (ref "Logo Bot") (pin "0") (pinfunction "0_0") (pintype "passive"))
    )
    (net (code "86") (name "unconnected-(Logo Lora Bot-Pad0)") (class "Default")
      (node (ref "Logo Lora Bot") (pin "0") (pinfunction "0_0") (pintype "passive"))
    )
    (net (code "87") (name "unconnected-(Logo Lora Top-Pad0)") (class "Default")
      (node (ref "Logo Lora Top") (pin "0") (pinfunction "0_0") (pintype "passive"))
    )
    (net (code "88") (name "unconnected-(Logo Top-Pad0)") (class "Default")
      (node (ref "Logo Top") (pin "0") (pinfunction "0_0") (pintype "passive"))
    )
    (net (code "89") (name "unconnected-(R5-Pad1)") (class "Default")
      (node (ref "R5") (pin "1") (pinfunction "1_1") (pintype "passive+no_connect"))
    )
    (net (code "90") (name "unconnected-(R5-Pad8)") (class "Default")
      (node (ref "R5") (pin "8") (pinfunction "8_8") (pintype "passive+no_connect"))
    )
    (net (code "91") (name "unconnected-(U1-RFO_LF-Pad28)") (class "Default")
      (node (ref "U1") (pin "28") (pinfunction "RFO_LF_28") (pintype "passive+no_connect"))
    )
    (net (code "92") (name "unconnected-(U1-XTB-Pad6)") (class "Default")
      (node (ref "U1") (pin "6") (pinfunction "XTB_6") (pintype "passive+no_connect"))
    )
  )
)
